# VCO_HMC8364.net
KiCad netlist of a schematic drawn in Altium Designer
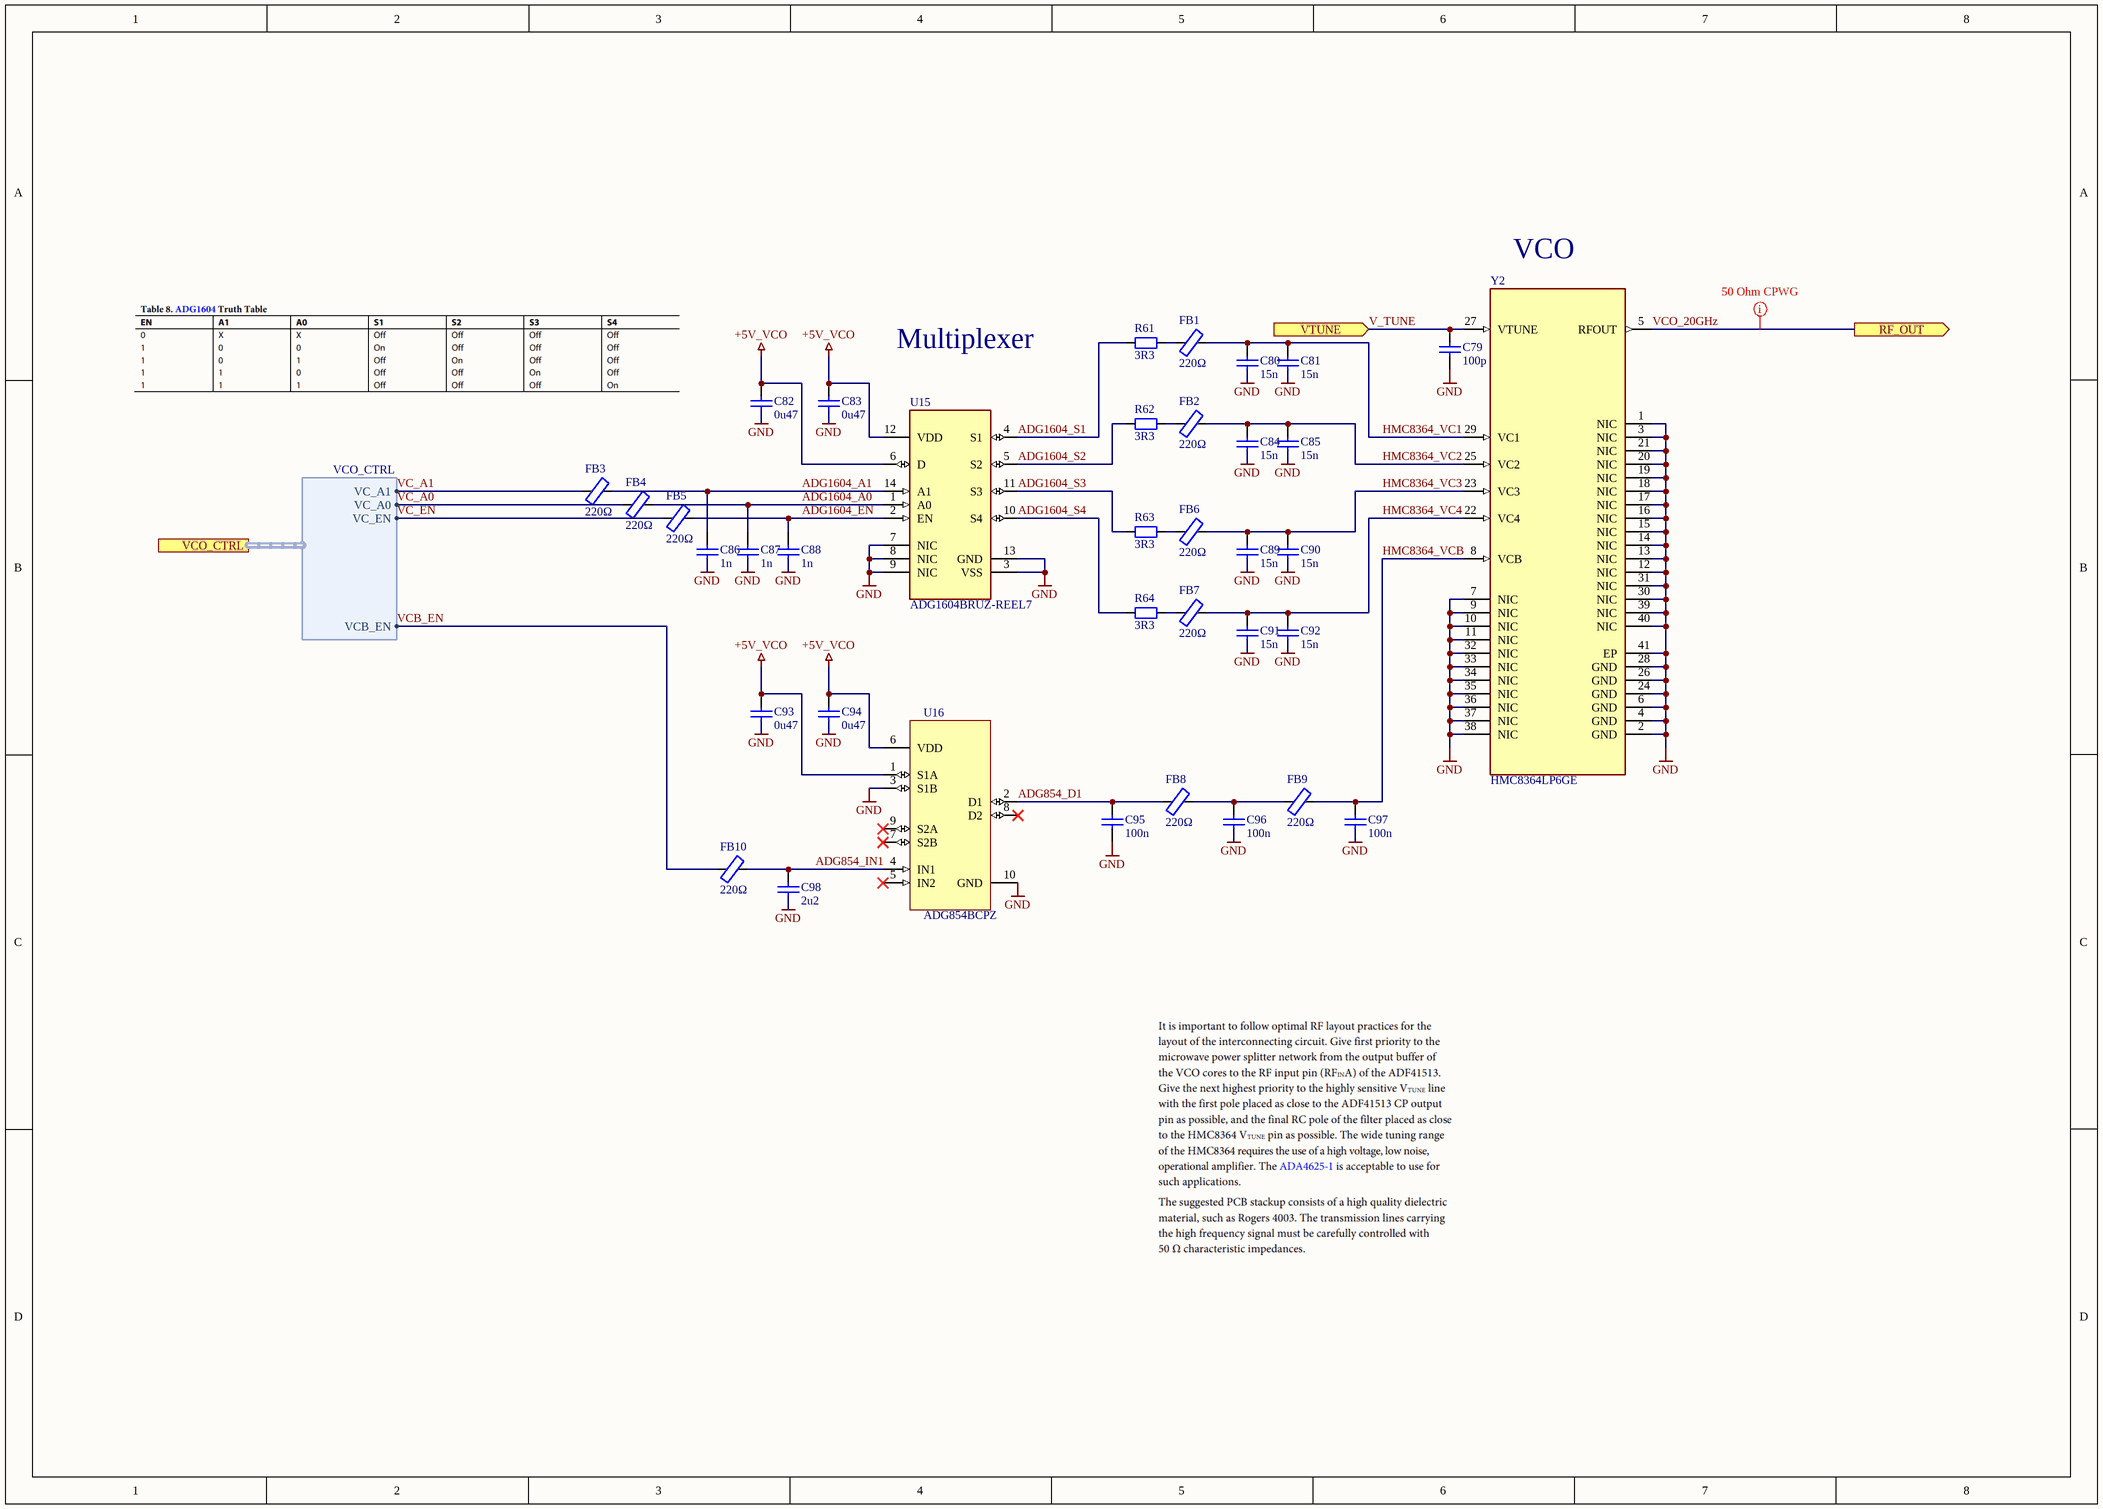
[diagram p0: VCO_HMC8364.SchDoc]

(export (version "E")
  (design (tool "Eeschema 10.0.6"))
  (components
    (comp (ref "C79")
      (value "100p")
      (footprint "C_0402_1005Metric_IPC_N")
      (description "Generic MLCC with 0402 Footprint")
      (libsource (lib "database_library") (part "Capacitor_unpol"))
    )
    (comp (ref "C80")
      (value "15n")
      (footprint "C_0402_1005Metric_IPC_N")
      (description "Generic MLCC with 0402 Footprint")
      (libsource (lib "database_library") (part "Capacitor_unpol"))
    )
    (comp (ref "C81")
      (value "15n")
      (footprint "C_0402_1005Metric_IPC_N")
      (description "Generic MLCC with 0402 Footprint")
      (libsource (lib "database_library") (part "Capacitor_unpol"))
    )
    (comp (ref "C82")
      (value "0u47")
      (footprint "C_0402_1005Metric_IPC_N")
      (description "Generic MLCC with 0402 Footprint")
      (libsource (lib "database_library") (part "Capacitor_unpol"))
    )
    (comp (ref "C83")
      (value "0u47")
      (footprint "C_0402_1005Metric_IPC_N")
      (description "Generic MLCC with 0402 Footprint")
      (fields (field (name "TOLERANCE") "10%"))
      (libsource (lib "database_library") (part "Capacitor_unpol"))
    )
    (comp (ref "C84")
      (value "15n")
      (footprint "C_0402_1005Metric_IPC_N")
      (description "Generic MLCC with 0402 Footprint")
      (libsource (lib "database_library") (part "Capacitor_unpol"))
    )
    (comp (ref "C85")
      (value "15n")
      (footprint "C_0402_1005Metric_IPC_N")
      (description "Generic MLCC with 0402 Footprint")
      (libsource (lib "database_library") (part "Capacitor_unpol"))
    )
    (comp (ref "C86")
      (value "1n")
      (footprint "C_0402_1005Metric_IPC_N")
      (description "Generic MLCC with 0402 Footprint")
      (libsource (lib "database_library") (part "Capacitor_unpol"))
    )
    (comp (ref "C87")
      (value "1n")
      (footprint "C_0402_1005Metric_IPC_N")
      (description "Generic MLCC with 0402 Footprint")
      (libsource (lib "database_library") (part "Capacitor_unpol"))
    )
    (comp (ref "C88")
      (value "1n")
      (footprint "C_0402_1005Metric_IPC_N")
      (description "Generic MLCC with 0402 Footprint")
      (libsource (lib "database_library") (part "Capacitor_unpol"))
    )
    (comp (ref "C89")
      (value "15n")
      (footprint "C_0402_1005Metric_IPC_N")
      (description "Generic MLCC with 0402 Footprint")
      (libsource (lib "database_library") (part "Capacitor_unpol"))
    )
    (comp (ref "C90")
      (value "15n")
      (footprint "C_0402_1005Metric_IPC_N")
      (description "Generic MLCC with 0402 Footprint")
      (libsource (lib "database_library") (part "Capacitor_unpol"))
    )
    (comp (ref "C91")
      (value "15n")
      (footprint "C_0402_1005Metric_IPC_N")
      (description "Generic MLCC with 0402 Footprint")
      (libsource (lib "database_library") (part "Capacitor_unpol"))
    )
    (comp (ref "C92")
      (value "15n")
      (footprint "C_0402_1005Metric_IPC_N")
      (description "Generic MLCC with 0402 Footprint")
      (libsource (lib "database_library") (part "Capacitor_unpol"))
    )
    (comp (ref "C93")
      (value "0u47")
      (footprint "C_0402_1005Metric_IPC_N")
      (description "Generic MLCC with 0402 Footprint")
      (libsource (lib "database_library") (part "Capacitor_unpol"))
    )
    (comp (ref "C94")
      (value "0u47")
      (footprint "C_0402_1005Metric_IPC_N")
      (description "Generic MLCC with 0402 Footprint")
      (fields (field (name "TOLERANCE") "10%"))
      (libsource (lib "database_library") (part "Capacitor_unpol"))
    )
    (comp (ref "C95")
      (value "100n")
      (footprint "C_0402_1005Metric_IPC_N")
      (description "Generic MLCC with 0402 Footprint")
      (fields (field (name "TOLERANCE") "10%"))
      (libsource (lib "database_library") (part "Capacitor_unpol"))
    )
    (comp (ref "C96")
      (value "100n")
      (footprint "C_0402_1005Metric_IPC_N")
      (description "Generic MLCC with 0402 Footprint")
      (fields (field (name "TOLERANCE") "10%"))
      (libsource (lib "database_library") (part "Capacitor_unpol"))
    )
    (comp (ref "C97")
      (value "100n")
      (footprint "C_0402_1005Metric_IPC_N")
      (description "Generic MLCC with 0402 Footprint")
      (fields (field (name "TOLERANCE") "10%"))
      (libsource (lib "database_library") (part "Capacitor_unpol"))
    )
    (comp (ref "C98")
      (value "2u2")
      (footprint "C_0402_1005Metric_IPC_N")
      (description "Generic MLCC with 0402 Footprint")
      (libsource (lib "database_library") (part "Capacitor_unpol"))
    )
    (comp (ref "FB1")
      (value "220Ω")
      (footprint "L_0402_1005Metric_IPC_N")
      (description "Ferrite Beads, 220Ω, 0.3A, *, 700m, *, 0402")
      (fields
        (field (name "MANUFACTURER") "Murata Electronics")
        (field (name "MANUFACTURER PART NUMBER") "BLM15GG221SN1D")
      )
      (libsource (lib "database_library") (part "Ferrite_Beads"))
    )
    (comp (ref "FB2")
      (value "220Ω")
      (footprint "L_0402_1005Metric_IPC_N")
      (description "Ferrite Beads, 220Ω, 0.3A, *, 700m, *, 0402")
      (fields
        (field (name "MANUFACTURER") "Murata Electronics")
        (field (name "MANUFACTURER PART NUMBER") "BLM15GG221SN1D")
      )
      (libsource (lib "database_library") (part "Ferrite_Beads"))
    )
    (comp (ref "FB3")
      (value "220Ω")
      (footprint "L_0402_1005Metric_IPC_N")
      (description "Ferrite Beads, 220Ω, 0.3A, *, 700m, *, 0402")
      (fields
        (field (name "MANUFACTURER") "Murata Electronics")
        (field (name "MANUFACTURER PART NUMBER") "BLM15GG221SN1D")
      )
      (libsource (lib "database_library") (part "Ferrite_Beads"))
    )
    (comp (ref "FB4")
      (value "220Ω")
      (footprint "L_0402_1005Metric_IPC_N")
      (description "Ferrite Beads, 220Ω, 0.3A, *, 700m, *, 0402")
      (fields
        (field (name "MANUFACTURER") "Murata Electronics")
        (field (name "MANUFACTURER PART NUMBER") "BLM15GG221SN1D")
      )
      (libsource (lib "database_library") (part "Ferrite_Beads"))
    )
    (comp (ref "FB5")
      (value "220Ω")
      (footprint "L_0402_1005Metric_IPC_N")
      (description "Ferrite Beads, 220Ω, 0.3A, *, 700m, *, 0402")
      (fields
        (field (name "MANUFACTURER") "Murata Electronics")
        (field (name "MANUFACTURER PART NUMBER") "BLM15GG221SN1D")
      )
      (libsource (lib "database_library") (part "Ferrite_Beads"))
    )
    (comp (ref "FB6")
      (value "220Ω")
      (footprint "L_0402_1005Metric_IPC_N")
      (description "Ferrite Beads, 220Ω, 0.3A, *, 700m, *, 0402")
      (fields
        (field (name "MANUFACTURER") "Murata Electronics")
        (field (name "MANUFACTURER PART NUMBER") "BLM15GG221SN1D")
      )
      (libsource (lib "database_library") (part "Ferrite_Beads"))
    )
    (comp (ref "FB7")
      (value "220Ω")
      (footprint "L_0402_1005Metric_IPC_N")
      (description "Ferrite Beads, 220Ω, 0.3A, *, 700m, *, 0402")
      (fields
        (field (name "MANUFACTURER") "Murata Electronics")
        (field (name "MANUFACTURER PART NUMBER") "BLM15GG221SN1D")
      )
      (libsource (lib "database_library") (part "Ferrite_Beads"))
    )
    (comp (ref "FB8")
      (value "220Ω")
      (footprint "L_0402_1005Metric_IPC_N")
      (description "Ferrite Beads, 220Ω, 0.3A, *, 700m, *, 0402")
      (fields
        (field (name "MANUFACTURER") "Murata Electronics")
        (field (name "MANUFACTURER PART NUMBER") "BLM15GG221SN1D")
      )
      (libsource (lib "database_library") (part "Ferrite_Beads"))
    )
    (comp (ref "FB9")
      (value "220Ω")
      (footprint "L_0402_1005Metric_IPC_N")
      (description "Ferrite Beads, 220Ω, 0.3A, *, 700m, *, 0402")
      (fields
        (field (name "MANUFACTURER") "Murata Electronics")
        (field (name "MANUFACTURER PART NUMBER") "BLM15GG221SN1D")
      )
      (libsource (lib "database_library") (part "Ferrite_Beads"))
    )
    (comp (ref "FB10")
      (value "220Ω")
      (footprint "L_0402_1005Metric_IPC_N")
      (description "Ferrite Beads, 220Ω, 0.3A, *, 700m, *, 0402")
      (fields
        (field (name "MANUFACTURER") "Murata Electronics")
        (field (name "MANUFACTURER PART NUMBER") "BLM15GG221SN1D")
      )
      (libsource (lib "database_library") (part "Ferrite_Beads"))
    )
    (comp (ref "R61")
      (value "3R3")
      (footprint "R_0402_1005Metric_IPC_N")
      (description "Generic Chip Resistor with 0402 Footprint")
      (libsource (lib "database_library") (part "Resistor"))
    )
    (comp (ref "R62")
      (value "3R3")
      (footprint "R_0402_1005Metric_IPC_N")
      (description "Generic Chip Resistor with 0402 Footprint")
      (libsource (lib "database_library") (part "Resistor"))
    )
    (comp (ref "R63")
      (value "3R3")
      (footprint "R_0402_1005Metric_IPC_N")
      (description "Generic Chip Resistor with 0402 Footprint")
      (libsource (lib "database_library") (part "Resistor"))
    )
    (comp (ref "R64")
      (value "3R3")
      (footprint "R_0402_1005Metric_IPC_N")
      (description "Generic Chip Resistor with 0402 Footprint")
      (libsource (lib "database_library") (part "Resistor"))
    )
    (comp (ref "U15")
      (value "ADG1604BRUZ-REEL7")
      (footprint "TSSOP65P640X120-14N")
      (fields (field (name "MANUFACTURER") "Analog Devices"))
      (libsource (lib "database_library") (part "ADG1604BRUZ"))
    )
    (comp (ref "U16")
      (value "ADG854BCPZ")
      (footprint "LFCSP_UQ-10-1EP_1.3x1.6mm_P0.4mm_IPC_N")
      (fields (field (name "MANUFACTURER") "Analog Devices"))
      (libsource (lib "database_library") (part "ADG854BCPZ"))
    )
    (comp (ref "Y2")
      (value "HMC8364LP6GE")
      (footprint "LFCSP-40-1EP_6x6mm_P0.5mm_EP4.7x4.7mm_IPC_N")
      (description "VCO Oscillators Custom DRT Quad Band VCO 18.2- 26.5 GHz")
      (fields
        (field (name "MOUSER PART NUMBER") "584-HMC862ALP3E")
        (field (name "MANUFACTURER_PART_NUMBER") "HMC862ALP3E")
      )
      (libsource (lib "database_library") (part "HMC8364LP6GE"))
    )
  )
  (nets
    (net (code "2") (name "+5V_VCO") (class "Default")
      (node (ref "C82") (pin "2") (pinfunction "2_2") (pintype "passive"))
      (node (ref "C83") (pin "2") (pinfunction "2_2") (pintype "passive"))
      (node (ref "C93") (pin "2") (pinfunction "2_2") (pintype "passive"))
      (node (ref "C94") (pin "2") (pinfunction "2_2") (pintype "passive"))
      (node (ref "U15") (pin "12") (pinfunction "VDD_12") (pintype "passive"))
      (node (ref "U15") (pin "6") (pinfunction "D_6") (pintype "bidirectional"))
      (node (ref "U16") (pin "1") (pinfunction "S1A_1") (pintype "bidirectional"))
      (node (ref "U16") (pin "6") (pinfunction "VDD_6") (pintype "passive"))
    )
    (net (code "3") (name "/ADG854_D1") (class "Default")
      (node (ref "C95") (pin "2") (pinfunction "2_2") (pintype "passive"))
      (node (ref "FB8") (pin "1") (pinfunction "1_1") (pintype "passive"))
      (node (ref "U16") (pin "2") (pinfunction "D1_2") (pintype "bidirectional"))
    )
    (net (code "4") (name "/ADG854_IN1") (class "Default")
      (node (ref "C98") (pin "2") (pinfunction "2_2") (pintype "passive"))
      (node (ref "FB10") (pin "2") (pinfunction "2_2") (pintype "passive"))
      (node (ref "U16") (pin "4") (pinfunction "IN1_4") (pintype "input"))
    )
    (net (code "5") (name "/ADG1604_A0") (class "Default")
      (node (ref "C87") (pin "2") (pinfunction "2_2") (pintype "passive"))
      (node (ref "FB4") (pin "2") (pinfunction "2_2") (pintype "passive"))
      (node (ref "U15") (pin "1") (pinfunction "A0_1") (pintype "input"))
    )
    (net (code "6") (name "/ADG1604_A1") (class "Default")
      (node (ref "C86") (pin "2") (pinfunction "2_2") (pintype "passive"))
      (node (ref "FB3") (pin "2") (pinfunction "2_2") (pintype "passive"))
      (node (ref "U15") (pin "14") (pinfunction "A1_14") (pintype "input"))
    )
    (net (code "7") (name "/ADG1604_EN") (class "Default")
      (node (ref "C88") (pin "2") (pinfunction "2_2") (pintype "passive"))
      (node (ref "FB5") (pin "2") (pinfunction "2_2") (pintype "passive"))
      (node (ref "U15") (pin "2") (pinfunction "EN_2") (pintype "input"))
    )
    (net (code "8") (name "/ADG1604_S1") (class "Default")
      (node (ref "R61") (pin "1") (pinfunction "1_1") (pintype "passive"))
      (node (ref "U15") (pin "4") (pinfunction "S1_4") (pintype "bidirectional"))
    )
    (net (code "9") (name "/ADG1604_S2") (class "Default")
      (node (ref "R62") (pin "1") (pinfunction "1_1") (pintype "passive"))
      (node (ref "U15") (pin "5") (pinfunction "S2_5") (pintype "bidirectional"))
    )
    (net (code "10") (name "/ADG1604_S3") (class "Default")
      (node (ref "R63") (pin "1") (pinfunction "1_1") (pintype "passive"))
      (node (ref "U15") (pin "11") (pinfunction "S3_11") (pintype "bidirectional"))
    )
    (net (code "11") (name "/ADG1604_S4") (class "Default")
      (node (ref "R64") (pin "1") (pinfunction "1_1") (pintype "passive"))
      (node (ref "U15") (pin "10") (pinfunction "S4_10") (pintype "bidirectional"))
    )
    (net (code "12") (name "/HMC8364_VC1") (class "Default")
      (node (ref "C80") (pin "2") (pinfunction "2_2") (pintype "passive"))
      (node (ref "C81") (pin "2") (pinfunction "2_2") (pintype "passive"))
      (node (ref "FB1") (pin "2") (pinfunction "2_2") (pintype "passive"))
      (node (ref "Y2") (pin "29") (pinfunction "VC1_29") (pintype "input"))
    )
    (net (code "13") (name "/HMC8364_VC2") (class "Default")
      (node (ref "C84") (pin "2") (pinfunction "2_2") (pintype "passive"))
      (node (ref "C85") (pin "2") (pinfunction "2_2") (pintype "passive"))
      (node (ref "FB2") (pin "2") (pinfunction "2_2") (pintype "passive"))
      (node (ref "Y2") (pin "25") (pinfunction "VC2_25") (pintype "input"))
    )
    (net (code "14") (name "/HMC8364_VC3") (class "Default")
      (node (ref "C89") (pin "2") (pinfunction "2_2") (pintype "passive"))
      (node (ref "C90") (pin "2") (pinfunction "2_2") (pintype "passive"))
      (node (ref "FB6") (pin "2") (pinfunction "2_2") (pintype "passive"))
      (node (ref "Y2") (pin "23") (pinfunction "VC3_23") (pintype "input"))
    )
    (net (code "15") (name "/HMC8364_VC4") (class "Default")
      (node (ref "C91") (pin "2") (pinfunction "2_2") (pintype "passive"))
      (node (ref "C92") (pin "2") (pinfunction "2_2") (pintype "passive"))
      (node (ref "FB7") (pin "2") (pinfunction "2_2") (pintype "passive"))
      (node (ref "Y2") (pin "22") (pinfunction "VC4_22") (pintype "input"))
    )
    (net (code "16") (name "/HMC8364_VCB") (class "Default")
      (node (ref "C97") (pin "2") (pinfunction "2_2") (pintype "passive"))
      (node (ref "FB9") (pin "2") (pinfunction "2_2") (pintype "passive"))
      (node (ref "Y2") (pin "8") (pinfunction "VCB_8") (pintype "input"))
    )
    (net (code "17") (name "/VCB_EN") (class "Default")
      (node (ref "FB10") (pin "1") (pinfunction "1_1") (pintype "passive"))
    )
    (net (code "18") (name "/VCO_20GHz") (class "Default")
      (node (ref "Y2") (pin "5") (pinfunction "RFOUT_5") (pintype "output"))
    )
    (net (code "19") (name "/VC_A0") (class "Default")
      (node (ref "FB4") (pin "1") (pinfunction "1_1") (pintype "passive"))
    )
    (net (code "20") (name "/VC_A1") (class "Default")
      (node (ref "FB3") (pin "1") (pinfunction "1_1") (pintype "passive"))
    )
    (net (code "21") (name "/VC_EN") (class "Default")
      (node (ref "FB5") (pin "1") (pinfunction "1_1") (pintype "passive"))
    )
    (net (code "22") (name "/V_TUNE") (class "Default")
      (node (ref "C79") (pin "2") (pinfunction "2_2") (pintype "passive"))
      (node (ref "Y2") (pin "27") (pinfunction "VTUNE_27") (pintype "input"))
    )
    (net (code "24") (name "GND") (class "Default")
      (node (ref "C79") (pin "1") (pinfunction "1_1") (pintype "passive"))
      (node (ref "C80") (pin "1") (pinfunction "1_1") (pintype "passive"))
      (node (ref "C81") (pin "1") (pinfunction "1_1") (pintype "passive"))
      (node (ref "C82") (pin "1") (pinfunction "1_1") (pintype "passive"))
      (node (ref "C83") (pin "1") (pinfunction "1_1") (pintype "passive"))
      (node (ref "C84") (pin "1") (pinfunction "1_1") (pintype "passive"))
      (node (ref "C85") (pin "1") (pinfunction "1_1") (pintype "passive"))
      (node (ref "C86") (pin "1") (pinfunction "1_1") (pintype "passive"))
      (node (ref "C87") (pin "1") (pinfunction "1_1") (pintype "passive"))
      (node (ref "C88") (pin "1") (pinfunction "1_1") (pintype "passive"))
      (node (ref "C89") (pin "1") (pinfunction "1_1") (pintype "passive"))
      (node (ref "C90") (pin "1") (pinfunction "1_1") (pintype "passive"))
      (node (ref "C91") (pin "1") (pinfunction "1_1") (pintype "passive"))
      (node (ref "C92") (pin "1") (pinfunction "1_1") (pintype "passive"))
      (node (ref "C93") (pin "1") (pinfunction "1_1") (pintype "passive"))
      (node (ref "C94") (pin "1") (pinfunction "1_1") (pintype "passive"))
      (node (ref "C95") (pin "1") (pinfunction "1_1") (pintype "passive"))
      (node (ref "C96") (pin "1") (pinfunction "1_1") (pintype "passive"))
      (node (ref "C97") (pin "1") (pinfunction "1_1") (pintype "passive"))
      (node (ref "C98") (pin "1") (pinfunction "1_1") (pintype "passive"))
      (node (ref "U15") (pin "13") (pinfunction "GND_13") (pintype "passive"))
      (node (ref "U15") (pin "3") (pinfunction "VSS_3") (pintype "passive"))
      (node (ref "U15") (pin "7") (pinfunction "NIC_7") (pintype "passive"))
      (node (ref "U15") (pin "8") (pinfunction "NIC_8") (pintype "passive"))
      (node (ref "U15") (pin "9") (pinfunction "NIC_9") (pintype "passive"))
      (node (ref "U16") (pin "10") (pinfunction "GND_10") (pintype "passive"))
      (node (ref "U16") (pin "3") (pinfunction "S1B_3") (pintype "bidirectional"))
      (node (ref "Y2") (pin "1") (pinfunction "NIC_1") (pintype "passive"))
      (node (ref "Y2") (pin "10") (pinfunction "NIC_10") (pintype "passive"))
      (node (ref "Y2") (pin "11") (pinfunction "NIC_11") (pintype "passive"))
      (node (ref "Y2") (pin "12") (pinfunction "NIC_12") (pintype "passive"))
      (node (ref "Y2") (pin "13") (pinfunction "NIC_13") (pintype "passive"))
      (node (ref "Y2") (pin "14") (pinfunction "NIC_14") (pintype "passive"))
      (node (ref "Y2") (pin "15") (pinfunction "NIC_15") (pintype "passive"))
      (node (ref "Y2") (pin "16") (pinfunction "NIC_16") (pintype "passive"))
      (node (ref "Y2") (pin "17") (pinfunction "NIC_17") (pintype "passive"))
      (node (ref "Y2") (pin "18") (pinfunction "NIC_18") (pintype "passive"))
      (node (ref "Y2") (pin "19") (pinfunction "NIC_19") (pintype "passive"))
      (node (ref "Y2") (pin "2") (pinfunction "GND_2") (pintype "passive"))
      (node (ref "Y2") (pin "20") (pinfunction "NIC_20") (pintype "passive"))
      (node (ref "Y2") (pin "21") (pinfunction "NIC_21") (pintype "passive"))
      (node (ref "Y2") (pin "24") (pinfunction "GND_24") (pintype "passive"))
      (node (ref "Y2") (pin "26") (pinfunction "GND_26") (pintype "passive"))
      (node (ref "Y2") (pin "28") (pinfunction "GND_28") (pintype "passive"))
      (node (ref "Y2") (pin "3") (pinfunction "NIC_3") (pintype "passive"))
      (node (ref "Y2") (pin "30") (pinfunction "NIC_30") (pintype "passive"))
      (node (ref "Y2") (pin "31") (pinfunction "NIC_31") (pintype "passive"))
      (node (ref "Y2") (pin "32") (pinfunction "NIC_32") (pintype "passive"))
      (node (ref "Y2") (pin "33") (pinfunction "NIC_33") (pintype "passive"))
      (node (ref "Y2") (pin "34") (pinfunction "NIC_34") (pintype "passive"))
      (node (ref "Y2") (pin "35") (pinfunction "NIC_35") (pintype "passive"))
      (node (ref "Y2") (pin "36") (pinfunction "NIC_36") (pintype "passive"))
      (node (ref "Y2") (pin "37") (pinfunction "NIC_37") (pintype "passive"))
      (node (ref "Y2") (pin "38") (pinfunction "NIC_38") (pintype "passive"))
      (node (ref "Y2") (pin "39") (pinfunction "NIC_39") (pintype "passive"))
      (node (ref "Y2") (pin "4") (pinfunction "GND_4") (pintype "passive"))
      (node (ref "Y2") (pin "40") (pinfunction "NIC_40") (pintype "passive"))
      (node (ref "Y2") (pin "41") (pinfunction "EP_41") (pintype "passive"))
      (node (ref "Y2") (pin "6") (pinfunction "GND_6") (pintype "passive"))
      (node (ref "Y2") (pin "7") (pinfunction "NIC_7") (pintype "passive"))
      (node (ref "Y2") (pin "9") (pinfunction "NIC_9") (pintype "passive"))
    )
    (net (code "25") (name "Net-(C96-Pad2)") (class "Default")
      (node (ref "C96") (pin "2") (pinfunction "2_2") (pintype "passive"))
      (node (ref "FB8") (pin "2") (pinfunction "2_2") (pintype "passive"))
      (node (ref "FB9") (pin "1") (pinfunction "1_1") (pintype "passive"))
    )
    (net (code "26") (name "Net-(FB1-Pad1)") (class "Default")
      (node (ref "FB1") (pin "1") (pinfunction "1_1") (pintype "passive"))
      (node (ref "R61") (pin "2") (pinfunction "2_2") (pintype "passive"))
    )
    (net (code "27") (name "Net-(FB2-Pad1)") (class "Default")
      (node (ref "FB2") (pin "1") (pinfunction "1_1") (pintype "passive"))
      (node (ref "R62") (pin "2") (pinfunction "2_2") (pintype "passive"))
    )
    (net (code "28") (name "Net-(FB6-Pad1)") (class "Default")
      (node (ref "FB6") (pin "1") (pinfunction "1_1") (pintype "passive"))
      (node (ref "R63") (pin "2") (pinfunction "2_2") (pintype "passive"))
    )
    (net (code "29") (name "Net-(FB7-Pad1)") (class "Default")
      (node (ref "FB7") (pin "1") (pinfunction "1_1") (pintype "passive"))
      (node (ref "R64") (pin "2") (pinfunction "2_2") (pintype "passive"))
    )
    (net (code "30") (name "unconnected-(U16-D2-Pad8)") (class "Default")
      (node (ref "U16") (pin "8") (pinfunction "D2_8") (pintype "bidirectional+no_connect"))
    )
    (net (code "31") (name "unconnected-(U16-IN2-Pad5)") (class "Default")
      (node (ref "U16") (pin "5") (pinfunction "IN2_5") (pintype "input+no_connect"))
    )
    (net (code "32") (name "unconnected-(U16-S2A-Pad9)") (class "Default")
      (node (ref "U16") (pin "9") (pinfunction "S2A_9") (pintype "bidirectional+no_connect"))
    )
    (net (code "33") (name "unconnected-(U16-S2B-Pad7)") (class "Default")
      (node (ref "U16") (pin "7") (pinfunction "S2B_7") (pintype "bidirectional+no_connect"))
    )
  )
)
